# PR2017-DC_LoadMotherBoard.net
KiCad netlist of a schematic drawn in Altium Designer
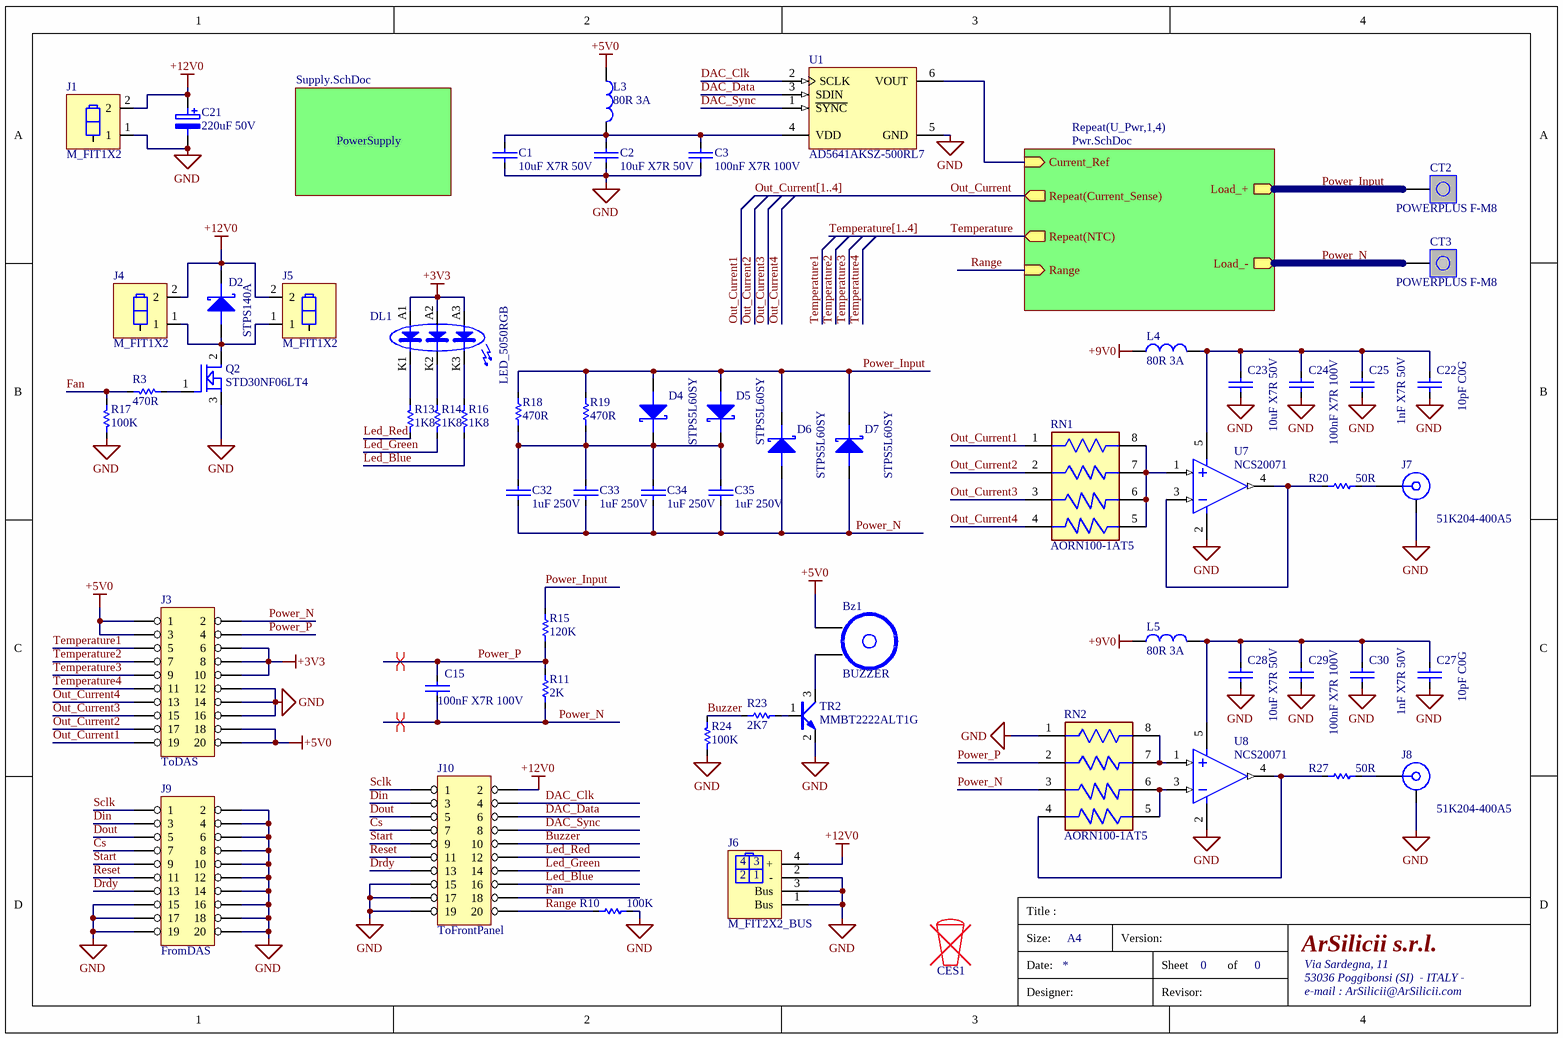
[diagram p0: PR2017-DC_LoadMotherBoard.SchDoc]

(export (version "E")
  (design (tool "Eeschema 10.0.6"))
  (components
    (comp (ref "Bz1")
      (value "BUZZER")
      (footprint "CB13PA")
      (description "Buzzer")
      (libsource (lib "Library_20-02-20") (part "BUZZER"))
    )
    (comp (ref "C1")
      (value "10uF X7R 50V")
      (footprint "1206")
      (description "Capacità")
      (fields
        (field (name "1 SUPPLIER PART NUMBER") "CL31B106KBHNNNE")
        (field (name "ARSILICII PART NUMBER") "CPC0232011")
      )
      (libsource (lib "Library_20-02-20") (part "CAP_10uF X7R 50V_1206"))
    )
    (comp (ref "C2")
      (value "10uF X7R 50V")
      (footprint "1206")
      (description "Capacità")
      (fields
        (field (name "1 SUPPLIER PART NUMBER") "CL31B106KBHNNNE")
        (field (name "ARSILICII PART NUMBER") "CPC0232011")
      )
      (libsource (lib "Library_20-02-20") (part "CAP_10uF X7R 50V_1206"))
    )
    (comp (ref "C3")
      (value "100nF X7R 100V")
      (footprint "0805")
      (description "Capacità")
      (fields
        (field (name "1 SUPPLIER PART NUMBER") "CL21B104KCFSFNG")
        (field (name "2 SUPPLIER PART NUMBER") "1907331")
      )
      (libsource (lib "Library_20-02-20") (part "CAP_100nF X7R 100V_0805"))
    )
    (comp (ref "C15")
      (value "100nF X7R 100V")
      (footprint "0805")
      (description "Capacità")
      (fields
        (field (name "1 SUPPLIER PART NUMBER") "CL21B104KCFSFNG")
        (field (name "2 SUPPLIER PART NUMBER") "1907331")
      )
      (libsource (lib "Library_20-02-20") (part "CAP_100nF X7R 100V_0805"))
    )
    (comp (ref "C21")
      (value "220uF 50V")
      (footprint "C_G55")
      (description "Capacità polarizzata")
      (fields
        (field (name "2 SUPPLIER PART NUMBER") "5194346")
        (field (name "ARSILICII PART NUMBER") "CPC0402221")
      )
      (libsource (lib "Library_20-02-20") (part "CAP_EL_220uF 50V"))
    )
    (comp (ref "C22")
      (value "10pF C0G")
      (footprint "0805")
      (description "Capacità")
      (fields (field (name "ARSILICII PART NUMBER") "CPC0614010"))
      (libsource (lib "Library_20-02-20") (part "CAP_10pF C0G_0805"))
    )
    (comp (ref "C23")
      (value "10uF X7R 50V")
      (footprint "1206")
      (description "Capacità")
      (fields
        (field (name "1 SUPPLIER PART NUMBER") "CL31B106KBHNNNE")
        (field (name "ARSILICII PART NUMBER") "CPC0232011")
      )
      (libsource (lib "Library_20-02-20") (part "CAP_10uF X7R 50V_1206"))
    )
    (comp (ref "C24")
      (value "100nF X7R 100V")
      (footprint "0805")
      (description "Capacità")
      (fields
        (field (name "1 SUPPLIER PART NUMBER") "CL21B104KCFSFNG")
        (field (name "2 SUPPLIER PART NUMBER") "1907331")
      )
      (libsource (lib "Library_20-02-20") (part "CAP_100nF X7R 100V_0805"))
    )
    (comp (ref "C25")
      (value "1nF X7R 50V")
      (footprint "0603")
      (description "Capacità")
      (fields
        (field (name "1 SUPPLIER PART NUMBER") "CC0603JRX7R9BB102")
        (field (name "ARSILICII PART NUMBER") "CPC0263001")
      )
      (libsource (lib "Library_20-02-20") (part "CAP_1nF X7R 50V_0603"))
    )
    (comp (ref "C27")
      (value "10pF C0G")
      (footprint "0805")
      (description "Capacità")
      (fields (field (name "ARSILICII PART NUMBER") "CPC0614010"))
      (libsource (lib "Library_20-02-20") (part "CAP_10pF C0G_0805"))
    )
    (comp (ref "C28")
      (value "10uF X7R 50V")
      (footprint "1206")
      (description "Capacità")
      (fields
        (field (name "1 SUPPLIER PART NUMBER") "CL31B106KBHNNNE")
        (field (name "ARSILICII PART NUMBER") "CPC0232011")
      )
      (libsource (lib "Library_20-02-20") (part "CAP_10uF X7R 50V_1206"))
    )
    (comp (ref "C29")
      (value "100nF X7R 100V")
      (footprint "0805")
      (description "Capacità")
      (fields
        (field (name "1 SUPPLIER PART NUMBER") "CL21B104KCFSFNG")
        (field (name "2 SUPPLIER PART NUMBER") "1907331")
      )
      (libsource (lib "Library_20-02-20") (part "CAP_100nF X7R 100V_0805"))
    )
    (comp (ref "C30")
      (value "1nF X7R 50V")
      (footprint "0603")
      (description "Capacità")
      (fields
        (field (name "1 SUPPLIER PART NUMBER") "CC0603JRX7R9BB102")
        (field (name "ARSILICII PART NUMBER") "CPC0263001")
      )
      (libsource (lib "Library_20-02-20") (part "CAP_1nF X7R 50V_0603"))
    )
    (comp (ref "C32")
      (value "1uF 250V")
      (footprint "POL-P15")
      (description "Capacità poliestere")
      (fields
        (field (name "ARSILICII PART NUMBER") "CPC0502002")
        (field (name "MANUFACTURER PART NUMBER") "MKTR60II4100ZB30K")
      )
      (libsource (lib "Library_20-02-20") (part "CAP_POL_1uF 250V P.15"))
    )
    (comp (ref "C33")
      (value "1uF 250V")
      (footprint "POL-P15")
      (description "Capacità poliestere")
      (fields
        (field (name "ARSILICII PART NUMBER") "CPC0502002")
        (field (name "MANUFACTURER PART NUMBER") "MKTR60II4100ZB30K")
      )
      (libsource (lib "Library_20-02-20") (part "CAP_POL_1uF 250V P.15"))
    )
    (comp (ref "C34")
      (value "1uF 250V")
      (footprint "POL-P15")
      (description "Capacità poliestere")
      (fields
        (field (name "ARSILICII PART NUMBER") "CPC0502002")
        (field (name "MANUFACTURER PART NUMBER") "MKTR60II4100ZB30K")
      )
      (libsource (lib "Library_20-02-20") (part "CAP_POL_1uF 250V P.15"))
    )
    (comp (ref "C35")
      (value "1uF 250V")
      (footprint "POL-P15")
      (description "Capacità poliestere")
      (fields
        (field (name "ARSILICII PART NUMBER") "CPC0502002")
        (field (name "MANUFACTURER PART NUMBER") "MKTR60II4100ZB30K")
      )
      (libsource (lib "Library_20-02-20") (part "CAP_POL_1uF 250V P.15"))
    )
    (comp (ref "CES1")
      (value "CESTINO")
      (footprint "Cestino1")
      (libsource (lib "Library_20-02-20") (part "CESTINO"))
    )
    (comp (ref "CT2")
      (value "POWERPLUS F-M8")
      (footprint "PowerPlus M8")
      (description "Singolo contatto")
      (fields
        (field (name "1 SUPPLIER PART NUMBER") "S98978")
        (field (name "ARSILICII PART NUMBER") "QC04000180")
      )
      (libsource (lib "Library_20-02-20") (part "PAD_POWERPLUS F-M8"))
    )
    (comp (ref "CT3")
      (value "POWERPLUS F-M8")
      (footprint "PowerPlus M8")
      (description "Singolo contatto")
      (fields
        (field (name "1 SUPPLIER PART NUMBER") "S98978")
        (field (name "ARSILICII PART NUMBER") "QC04000180")
      )
      (libsource (lib "Library_20-02-20") (part "PAD_POWERPLUS F-M8"))
    )
    (comp (ref "D2")
      (value "STPS140A")
      (footprint "SMA")
      (description "Diodo Schottky")
      (fields
        (field (name "MANUFACTURER") "STMicroelectronics")
        (field (name "1 SUPPLIER PART NUMBER") "STMSTPS140A")
      )
      (libsource (lib "Library_20-02-20") (part "DIODE SCHOTTKY_STPS140A"))
    )
    (comp (ref "D4")
      (value "STPS5L60SY")
      (footprint "SMC")
      (description "Automotive power Schottky rectifier")
      (fields (field (name "MANUFACTURER") "STM") (field (name "1 SUPPLIER PART NUMBER") "511-STPS5L60SY"))
      (libsource (lib "Library_20-02-20") (part "DIODE SCHOTTKY_STPS5L60SY"))
    )
    (comp (ref "D5")
      (value "STPS5L60SY")
      (footprint "SMC")
      (description "Automotive power Schottky rectifier")
      (fields (field (name "MANUFACTURER") "STM") (field (name "1 SUPPLIER PART NUMBER") "511-STPS5L60SY"))
      (libsource (lib "Library_20-02-20") (part "DIODE SCHOTTKY_STPS5L60SY"))
    )
    (comp (ref "D6")
      (value "STPS5L60SY")
      (footprint "SMC")
      (description "Automotive power Schottky rectifier")
      (fields (field (name "MANUFACTURER") "STM") (field (name "1 SUPPLIER PART NUMBER") "511-STPS5L60SY"))
      (libsource (lib "Library_20-02-20") (part "DIODE SCHOTTKY_STPS5L60SY"))
    )
    (comp (ref "D7")
      (value "STPS5L60SY")
      (footprint "SMC")
      (description "Automotive power Schottky rectifier")
      (fields (field (name "MANUFACTURER") "STM") (field (name "1 SUPPLIER PART NUMBER") "511-STPS5L60SY"))
      (libsource (lib "Library_20-02-20") (part "DIODE SCHOTTKY_STPS5L60SY"))
    )
    (comp (ref "DL1")
      (value "LED_5050RGB")
      (footprint "LED_5050RGB")
      (description "LED RGB")
      (libsource (lib "Library_20-02-20") (part "LED_5050RGB"))
    )
    (comp (ref "J1")
      (value "M_FIT1X2")
      (footprint "M_FIT_JR1X2V")
      (description "Mini Fit Junior 2 poli")
      (fields (field (name "ARSILICII PART NUMBER") "QA02006000") (field (name "MANUFACTURER") "Molex"))
      (libsource (lib "") (part "M_FIT1X2_1"))
    )
    (comp (ref "J3")
      (value "ToDAS")
      (footprint "IDC-20")
      (libsource (lib "Library_20-02-20") (part "HEADER 10X2"))
    )
    (comp (ref "J4")
      (value "M_FIT1X2")
      (footprint "M_FIT_JR1X2V")
      (description "Mini Fit Junior 2 poli")
      (fields (field (name "ARSILICII PART NUMBER") "QA02006000") (field (name "MANUFACTURER") "Molex"))
      (libsource (lib "") (part "M_FIT1X2_1"))
    )
    (comp (ref "J5")
      (value "M_FIT1X2")
      (footprint "M_FIT_JR1X2V")
      (description "Mini Fit Junior 2 poli")
      (fields (field (name "ARSILICII PART NUMBER") "QA02006000") (field (name "MANUFACTURER") "Molex"))
      (libsource (lib "Library_20-02-20") (part "M_FIT1X2"))
    )
    (comp (ref "J6")
      (value "M_FIT2X2_BUS")
      (footprint "M_FIT_JR2X2V")
      (description "Mini Fit Junior 4 poli")
      (fields
        (field (name "2 SUPPLIER PART NUMBER") "P6657I-04")
        (field (name "3 SUPPLIER PART NUMBER") "EY5900-W04ST")
      )
      (libsource (lib "Library_20-02-20") (part "M_FIT2X2_BUS"))
    )
    (comp (ref "J7")
      (value "51K204-400A5")
      (footprint "ROS-51K204-400A5_V")
      (description "BNC 50R Right Angle Jack, Panel Feedthrough, Up to 10 GHz, -55 to 155 degC")
      (fields (field (name "MANUFACTURER") "Rosenberger"))
      (libsource (lib "Altium Content Vault") (part "ROS-CN-1F-RF1"))
    )
    (comp (ref "J8")
      (value "51K204-400A5")
      (footprint "ROS-51K204-400A5_V")
      (description "BNC 50R Right Angle Jack, Panel Feedthrough, Up to 10 GHz, -55 to 155 degC")
      (fields (field (name "MANUFACTURER") "Rosenberger"))
      (libsource (lib "Altium Content Vault") (part "ROS-CN-1F-RF1"))
    )
    (comp (ref "J9")
      (value "FromDAS")
      (footprint "IDC-20")
      (libsource (lib "Library_20-02-20") (part "HEADER 10X2"))
    )
    (comp (ref "J10")
      (value "ToFrontPanel")
      (footprint "IDC-20")
      (libsource (lib "Library_20-02-20") (part "HEADER 10X2"))
    )
    (comp (ref "L3")
      (value "80R 3A")
      (footprint "1206")
      (description "Ferrite")
      (fields
        (field (name "1 SUPPLIER PART NUMBER") "3275550P")
        (field (name "ARSILICII PART NUMBER") "CPF0006000")
      )
      (libsource (lib "Library_20-02-20") (part "Ferrite 80R 3A"))
    )
    (comp (ref "L4")
      (value "80R 3A")
      (footprint "1206")
      (description "Ferrite")
      (fields
        (field (name "1 SUPPLIER PART NUMBER") "3275550P")
        (field (name "ARSILICII PART NUMBER") "CPF0006000")
      )
      (libsource (lib "Library_20-02-20") (part "Ferrite 80R 3A"))
    )
    (comp (ref "L5")
      (value "80R 3A")
      (footprint "1206")
      (description "Ferrite")
      (fields
        (field (name "1 SUPPLIER PART NUMBER") "3275550P")
        (field (name "ARSILICII PART NUMBER") "CPF0006000")
      )
      (libsource (lib "Library_20-02-20") (part "Ferrite 80R 3A"))
    )
    (comp (ref "Q2")
      (value "STD30NF06LT4")
      (footprint "DPAK")
      (description "N-CHANNEL 60V - 0.020 Ω - 28A IPAK/DPAK  STripFET™ II POWER MOSFET")
      (fields
        (field (name "1 SUPPLIER PART NUMBER") "STD30NF06LT4/STM")
        (field (name "ARSILICII PART NUMBER") "CPTP200030")
      )
      (libsource (lib "Library_20-02-20") (part "MOS-N STD30NF06"))
    )
    (comp (ref "R3")
      (value "470R")
      (footprint "0805")
      (description "Resistenza")
      (libsource (lib "Library_20-02-20") (part "RES_SMD"))
    )
    (comp (ref "R10")
      (value "100K")
      (footprint "0805")
      (description "Resistenza")
      (libsource (lib "Library_20-02-20") (part "RES_SMD"))
    )
    (comp (ref "R11")
      (value "2K")
      (footprint "2512")
      (description "Resistenza")
      (libsource (lib "Library_20-02-20") (part "RES_SMD"))
    )
    (comp (ref "R13")
      (value "1K8")
      (footprint "0805")
      (description "Resistenza")
      (libsource (lib "Library_20-02-20") (part "RES_SMD"))
    )
    (comp (ref "R14")
      (value "1K8")
      (footprint "0805")
      (description "Resistenza")
      (libsource (lib "Library_20-02-20") (part "RES_SMD"))
    )
    (comp (ref "R15")
      (value "120K")
      (footprint "2512")
      (description "Resistenza")
      (libsource (lib "Library_20-02-20") (part "RES_SMD"))
    )
    (comp (ref "R16")
      (value "1K8")
      (footprint "0805")
      (description "Resistenza")
      (libsource (lib "Library_20-02-20") (part "RES_SMD"))
    )
    (comp (ref "R17")
      (value "100K")
      (footprint "0805")
      (description "Resistenza")
      (libsource (lib "Library_20-02-20") (part "RES_SMD"))
    )
    (comp (ref "R18")
      (value "470R")
      (footprint "0805")
      (description "Resistenza")
      (libsource (lib "Library_20-02-20") (part "RES_SMD"))
    )
    (comp (ref "R19")
      (value "470R")
      (footprint "0805")
      (description "Resistenza")
      (libsource (lib "Library_20-02-20") (part "RES_SMD"))
    )
    (comp (ref "R20")
      (value "50R")
      (footprint "0805")
      (description "Resistenza")
      (libsource (lib "Library_20-02-20") (part "RES_SMD"))
    )
    (comp (ref "R23")
      (value "2K7")
      (footprint "0805")
      (description "Resistenza")
      (libsource (lib "Library_20-02-20") (part "RES_SMD"))
    )
    (comp (ref "R24")
      (value "100K")
      (footprint "0805")
      (description "Resistenza")
      (libsource (lib "Library_20-02-20") (part "RES_SMD"))
    )
    (comp (ref "R27")
      (value "50R")
      (footprint "0805")
      (description "Resistenza")
      (libsource (lib "Library_20-02-20") (part "RES_SMD"))
    )
    (comp (ref "RN1")
      (value "AORN100-1AT5")
      (footprint "FP-AORN100-1AT5-IPC_C")
      (description "RES NETWORK 4 RES MULT OHM 8SOIC")
      (fields (field (name "MANUFACTURER") "Vishay") (field (name "TOLERANCE") "0.1%"))
      (libsource (lib "Altium Content Vault") (part "8441eaa576eb2593bca60d5301712c1"))
    )
    (comp (ref "RN2")
      (value "AORN100-1AT5")
      (footprint "FP-AORN100-1AT5-IPC_C")
      (description "RES NETWORK 4 RES MULT OHM 8SOIC")
      (fields (field (name "MANUFACTURER") "Vishay") (field (name "TOLERANCE") "0.1%"))
      (libsource (lib "Altium Content Vault") (part "8441eaa576eb2593bca60d5301712c1"))
    )
    (comp (ref "TR2")
      (value "MMBT2222ALT1G")
      (footprint "SOT-23")
      (description "NPN Transistor")
      (fields
        (field (name "1 SUPPLIER PART NUMBER") "SCGMMBT2222ALT1G")
        (field (name "2 SUPPLIER PART NUMBER") "1459098")
      )
      (libsource (lib "Library_20-02-20") (part "NPN_MMBT2222ALT1G"))
    )
    (comp (ref "U1")
      (value "AD5641AKSZ-500RL7")
      (footprint "KS-6_L")
      (description "Single 14-Bit nanoDAC with SPI Interface, 5 V, <100 uA, -40 to +125 degC, KS-6, Pb-Free, Reel")
      (fields (field (name "GENERIC PART NUMBER") "AD5641") (field (name "MANUFACTURER") "Analog Devices"))
      (libsource (lib "Altium Content Vault") (part "ADI-AD5641-KS-6"))
    )
    (comp (ref "U7")
      (value "NCS20071")
      (footprint "SOT-553-5")
      (description "Rail-to-Rail Input/Output, 3 MHz Op Amps")
      (fields
        (field (name "1 SUPPLIER PART NUMBER") "MCP6021-E/SN-ND")
        (field (name "MANUFACTURER") "Microchip Technology")
      )
      (libsource (lib "Library_20-02-20") (part "NCS20071"))
    )
    (comp (ref "U8")
      (value "NCS20071")
      (footprint "SOT-553-5")
      (description "Rail-to-Rail Input/Output, 3 MHz Op Amps")
      (fields
        (field (name "1 SUPPLIER PART NUMBER") "MCP6021-E/SN-ND")
        (field (name "MANUFACTURER") "Microchip Technology")
      )
      (libsource (lib "Library_20-02-20") (part "NCS20071"))
    )
  )
  (nets
    (net (code "1") (name "+3V3") (class "Default")
      (node (ref "DL1") (pin "A1") (pinfunction "A1_A1") (pintype "passive"))
      (node (ref "DL1") (pin "A2") (pinfunction "A2_A2") (pintype "passive"))
      (node (ref "DL1") (pin "A3") (pinfunction "A3_A3") (pintype "passive"))
      (node (ref "J3") (pin "10") (pinfunction "10_10") (pintype "passive"))
      (node (ref "J3") (pin "6") (pinfunction "6_6") (pintype "passive"))
      (node (ref "J3") (pin "8") (pinfunction "8_8") (pintype "passive"))
    )
    (net (code "2") (name "+5V0") (class "Default")
      (node (ref "Bz1") (pin "1") (pinfunction "1_1") (pintype "passive"))
      (node (ref "J3") (pin "1") (pinfunction "1_1") (pintype "passive"))
      (node (ref "J3") (pin "18") (pinfunction "18_18") (pintype "passive"))
      (node (ref "J3") (pin "20") (pinfunction "20_20") (pintype "passive"))
      (node (ref "J3") (pin "3") (pinfunction "3_3") (pintype "passive"))
      (node (ref "L3") (pin "1") (pinfunction "1_1") (pintype "passive"))
    )
    (net (code "3") (name "+9V0") (class "Default")
      (node (ref "L4") (pin "1") (pinfunction "1_1") (pintype "passive"))
      (node (ref "L5") (pin "1") (pinfunction "1_1") (pintype "passive"))
    )
    (net (code "4") (name "+12V0") (class "Default")
      (node (ref "C21") (pin "1") (pintype "passive"))
      (node (ref "D2") (pin "K") (pinfunction "K_K") (pintype "passive"))
      (node (ref "J1") (pin "2") (pinfunction "2_2") (pintype "passive"))
      (node (ref "J10") (pin "2") (pinfunction "2_2") (pintype "passive"))
      (node (ref "J4") (pin "2") (pinfunction "2_2") (pintype "passive"))
      (node (ref "J5") (pin "2") (pinfunction "2_2") (pintype "passive"))
      (node (ref "J6") (pin "4") (pinfunction "+_4") (pintype "passive"))
    )
    (net (code "5") (name "/Buzzer") (class "Default")
      (node (ref "J10") (pin "10") (pinfunction "10_10") (pintype "passive"))
      (node (ref "R23") (pin "2") (pinfunction "2_2") (pintype "passive"))
      (node (ref "R24") (pin "2") (pinfunction "2_2") (pintype "passive"))
    )
    (net (code "6") (name "/Cs") (class "Default")
      (node (ref "J10") (pin "7") (pinfunction "7_7") (pintype "passive"))
      (node (ref "J9") (pin "7") (pinfunction "7_7") (pintype "passive"))
    )
    (net (code "7") (name "/Current_Ref") (class "Default")
      (node (ref "U1") (pin "6") (pinfunction "VOUT_6") (pintype "tri_state"))
    )
    (net (code "8") (name "/DAC_Clk") (class "Default")
      (node (ref "J10") (pin "4") (pinfunction "4_4") (pintype "passive"))
      (node (ref "U1") (pin "2") (pinfunction "SCLK_2") (pintype "input"))
    )
    (net (code "9") (name "/DAC_Data") (class "Default")
      (node (ref "J10") (pin "6") (pinfunction "6_6") (pintype "passive"))
      (node (ref "U1") (pin "3") (pinfunction "SDIN_3") (pintype "input"))
    )
    (net (code "10") (name "/DAC_Sync") (class "Default")
      (node (ref "J10") (pin "8") (pinfunction "8_8") (pintype "passive"))
      (node (ref "U1") (pin "1") (pinfunction "~{SYNC}_1") (pintype "input"))
    )
    (net (code "11") (name "/Din") (class "Default")
      (node (ref "J10") (pin "3") (pinfunction "3_3") (pintype "passive"))
      (node (ref "J9") (pin "3") (pinfunction "3_3") (pintype "passive"))
    )
    (net (code "12") (name "/Dout") (class "Default")
      (node (ref "J10") (pin "5") (pinfunction "5_5") (pintype "passive"))
      (node (ref "J9") (pin "5") (pinfunction "5_5") (pintype "passive"))
    )
    (net (code "13") (name "/Drdy") (class "Default")
      (node (ref "J10") (pin "13") (pinfunction "13_13") (pintype "passive"))
      (node (ref "J9") (pin "13") (pinfunction "13_13") (pintype "passive"))
    )
    (net (code "14") (name "/Fan") (class "Default")
      (node (ref "J10") (pin "18") (pinfunction "18_18") (pintype "passive"))
      (node (ref "R17") (pin "2") (pinfunction "2_2") (pintype "passive"))
      (node (ref "R3") (pin "2") (pinfunction "2_2") (pintype "passive"))
    )
    (net (code "15") (name "/Led_Blue") (class "Default")
      (node (ref "J10") (pin "16") (pinfunction "16_16") (pintype "passive"))
      (node (ref "R16") (pin "1") (pinfunction "1_1") (pintype "passive"))
    )
    (net (code "16") (name "/Led_Green") (class "Default")
      (node (ref "J10") (pin "14") (pinfunction "14_14") (pintype "passive"))
      (node (ref "R14") (pin "1") (pinfunction "1_1") (pintype "passive"))
    )
    (net (code "17") (name "/Led_Red") (class "Default")
      (node (ref "J10") (pin "12") (pinfunction "12_12") (pintype "passive"))
      (node (ref "R13") (pin "1") (pinfunction "1_1") (pintype "passive"))
    )
    (net (code "19") (name "/Out_Current1") (class "Default")
      (node (ref "J3") (pin "19") (pinfunction "19_19") (pintype "passive"))
      (node (ref "RN1") (pin "1") (pinfunction "1_1") (pintype "passive"))
    )
    (net (code "20") (name "/Out_Current2") (class "Default")
      (node (ref "J3") (pin "17") (pinfunction "17_17") (pintype "passive"))
      (node (ref "RN1") (pin "2") (pinfunction "2_2") (pintype "passive"))
    )
    (net (code "21") (name "/Out_Current3") (class "Default")
      (node (ref "J3") (pin "15") (pinfunction "15_15") (pintype "passive"))
      (node (ref "RN1") (pin "3") (pinfunction "3_3") (pintype "passive"))
    )
    (net (code "22") (name "/Out_Current4") (class "Default")
      (node (ref "J3") (pin "13") (pinfunction "13_13") (pintype "passive"))
      (node (ref "RN1") (pin "4") (pinfunction "4_4") (pintype "passive"))
    )
    (net (code "24") (name "/Power_Input") (class "Default")
      (node (ref "CT2") (pin "1") (pinfunction "1_1") (pintype "passive"))
      (node (ref "D4") (pin "A") (pinfunction "A_A") (pintype "passive"))
      (node (ref "D5") (pin "A") (pinfunction "A_A") (pintype "passive"))
      (node (ref "D6") (pin "K") (pinfunction "K_K") (pintype "passive"))
      (node (ref "D7") (pin "K") (pinfunction "K_K") (pintype "passive"))
      (node (ref "R15") (pin "1") (pinfunction "1_1") (pintype "passive"))
      (node (ref "R18") (pin "1") (pinfunction "1_1") (pintype "passive"))
      (node (ref "R19") (pin "1") (pinfunction "1_1") (pintype "passive"))
    )
    (net (code "25") (name "/Power_N") (class "Default")
      (node (ref "C15") (pin "2") (pintype "passive"))
      (node (ref "C32") (pin "2") (pintype "passive"))
      (node (ref "C33") (pin "2") (pintype "passive"))
      (node (ref "C34") (pin "2") (pintype "passive"))
      (node (ref "C35") (pin "2") (pintype "passive"))
      (node (ref "CT3") (pin "1") (pinfunction "1_1") (pintype "passive"))
      (node (ref "D6") (pin "A") (pinfunction "A_A") (pintype "passive"))
      (node (ref "D7") (pin "A") (pinfunction "A_A") (pintype "passive"))
      (node (ref "J3") (pin "2") (pinfunction "2_2") (pintype "passive"))
      (node (ref "R11") (pin "2") (pinfunction "2_2") (pintype "passive"))
      (node (ref "RN2") (pin "3") (pinfunction "3_3") (pintype "passive"))
    )
    (net (code "26") (name "/Power_P") (class "Default")
      (node (ref "C15") (pin "1") (pintype "passive"))
      (node (ref "J3") (pin "4") (pinfunction "4_4") (pintype "passive"))
      (node (ref "R11") (pin "1") (pinfunction "1_1") (pintype "passive"))
      (node (ref "R15") (pin "2") (pinfunction "2_2") (pintype "passive"))
      (node (ref "RN2") (pin "2") (pinfunction "2_2") (pintype "passive"))
    )
    (net (code "27") (name "/Range") (class "Default")
      (node (ref "J10") (pin "20") (pinfunction "20_20") (pintype "passive"))
      (node (ref "R10") (pin "2") (pinfunction "2_2") (pintype "passive"))
    )
    (net (code "28") (name "/Reset") (class "Default")
      (node (ref "J10") (pin "11") (pinfunction "11_11") (pintype "passive"))
      (node (ref "J9") (pin "11") (pinfunction "11_11") (pintype "passive"))
    )
    (net (code "29") (name "/Sclk") (class "Default")
      (node (ref "J10") (pin "1") (pinfunction "1_1") (pintype "passive"))
      (node (ref "J9") (pin "1") (pinfunction "1_1") (pintype "passive"))
    )
    (net (code "30") (name "/Start") (class "Default")
      (node (ref "J10") (pin "9") (pinfunction "9_9") (pintype "passive"))
      (node (ref "J9") (pin "9") (pinfunction "9_9") (pintype "passive"))
    )
    (net (code "32") (name "/Temperature1") (class "Default")
      (node (ref "J3") (pin "5") (pinfunction "5_5") (pintype "passive"))
    )
    (net (code "33") (name "/Temperature2") (class "Default")
      (node (ref "J3") (pin "7") (pinfunction "7_7") (pintype "passive"))
    )
    (net (code "34") (name "/Temperature3") (class "Default")
      (node (ref "J3") (pin "9") (pinfunction "9_9") (pintype "passive"))
    )
    (net (code "35") (name "/Temperature4") (class "Default")
      (node (ref "J3") (pin "11") (pinfunction "11_11") (pintype "passive"))
    )
    (net (code "37") (name "GND") (class "Default")
      (node (ref "C1") (pin "2") (pintype "passive"))
      (node (ref "C2") (pin "2") (pintype "passive"))
      (node (ref "C21") (pin "2") (pintype "passive"))
      (node (ref "C22") (pin "2") (pintype "passive"))
      (node (ref "C23") (pin "2") (pintype "passive"))
      (node (ref "C24") (pin "2") (pintype "passive"))
      (node (ref "C25") (pin "2") (pintype "passive"))
      (node (ref "C27") (pin "2") (pintype "passive"))
      (node (ref "C28") (pin "2") (pintype "passive"))
      (node (ref "C29") (pin "2") (pintype "passive"))
      (node (ref "C3") (pin "2") (pintype "passive"))
      (node (ref "C30") (pin "2") (pintype "passive"))
      (node (ref "J1") (pin "1") (pinfunction "1_1") (pintype "passive"))
      (node (ref "J10") (pin "15") (pinfunction "15_15") (pintype "passive"))
      (node (ref "J10") (pin "17") (pinfunction "17_17") (pintype "passive"))
      (node (ref "J10") (pin "19") (pinfunction "19_19") (pintype "passive"))
      (node (ref "J3") (pin "12") (pinfunction "12_12") (pintype "passive"))
      (node (ref "J3") (pin "14") (pinfunction "14_14") (pintype "passive"))
      (node (ref "J3") (pin "16") (pinfunction "16_16") (pintype "passive"))
      (node (ref "J6") (pin "1") (pinfunction "Bus_1") (pintype "passive"))
      (node (ref "J6") (pin "2") (pinfunction "-_2") (pintype "passive"))
      (node (ref "J6") (pin "3") (pinfunction "Bus_3") (pintype "passive"))
      (node (ref "J7") (pin "MH") (pinfunction "MH_MH") (pintype "passive"))
      (node (ref "J8") (pin "MH") (pinfunction "MH_MH") (pintype "passive"))
      (node (ref "J9") (pin "10") (pinfunction "10_10") (pintype "passive"))
      (node (ref "J9") (pin "12") (pinfunction "12_12") (pintype "passive"))
      (node (ref "J9") (pin "14") (pinfunction "14_14") (pintype "passive"))
      (node (ref "J9") (pin "15") (pinfunction "15_15") (pintype "passive"))
      (node (ref "J9") (pin "16") (pinfunction "16_16") (pintype "passive"))
      (node (ref "J9") (pin "17") (pinfunction "17_17") (pintype "passive"))
      (node (ref "J9") (pin "18") (pinfunction "18_18") (pintype "passive"))
      (node (ref "J9") (pin "19") (pinfunction "19_19") (pintype "passive"))
      (node (ref "J9") (pin "2") (pinfunction "2_2") (pintype "passive"))
      (node (ref "J9") (pin "20") (pinfunction "20_20") (pintype "passive"))
      (node (ref "J9") (pin "4") (pinfunction "4_4") (pintype "passive"))
      (node (ref "J9") (pin "6") (pinfunction "6_6") (pintype "passive"))
      (node (ref "J9") (pin "8") (pinfunction "8_8") (pintype "passive"))
      (node (ref "Q2") (pin "3") (pinfunction "SOURCE_3") (pintype "passive"))
      (node (ref "R10") (pin "1") (pinfunction "1_1") (pintype "passive"))
      (node (ref "R17") (pin "1") (pinfunction "1_1") (pintype "passive"))
      (node (ref "R24") (pin "1") (pinfunction "1_1") (pintype "passive"))
      (node (ref "RN2") (pin "1") (pinfunction "1_1") (pintype "passive"))
      (node (ref "TR2") (pin "2") (pinfunction "E_2") (pintype "passive"))
      (node (ref "U1") (pin "5") (pinfunction "GND_5") (pintype "power_in"))
      (node (ref "U7") (pin "2") (pintype "power_in"))
      (node (ref "U8") (pin "2") (pintype "power_in"))
    )
    (net (code "38") (name "Net-(C22-Pad1)") (class "Default")
      (node (ref "C22") (pin "1") (pintype "passive"))
      (node (ref "C23") (pin "1") (pintype "passive"))
      (node (ref "C24") (pin "1") (pintype "passive"))
      (node (ref "C25") (pin "1") (pintype "passive"))
      (node (ref "L4") (pin "2") (pinfunction "2_2") (pintype "passive"))
      (node (ref "U7") (pin "5") (pintype "power_in"))
    )
    (net (code "39") (name "Net-(C27-Pad1)") (class "Default")
      (node (ref "C27") (pin "1") (pintype "passive"))
      (node (ref "C28") (pin "1") (pintype "passive"))
      (node (ref "C29") (pin "1") (pintype "passive"))
      (node (ref "C30") (pin "1") (pintype "passive"))
      (node (ref "L5") (pin "2") (pinfunction "2_2") (pintype "passive"))
      (node (ref "U8") (pin "5") (pintype "power_in"))
    )
    (net (code "40") (name "Net-(C32-Pad1)") (class "Default")
      (node (ref "C32") (pin "1") (pintype "passive"))
      (node (ref "C33") (pin "1") (pintype "passive"))
      (node (ref "C34") (pin "1") (pintype "passive"))
      (node (ref "C35") (pin "1") (pintype "passive"))
      (node (ref "D4") (pin "K") (pinfunction "K_K") (pintype "passive"))
      (node (ref "D5") (pin "K") (pinfunction "K_K") (pintype "passive"))
      (node (ref "R18") (pin "2") (pinfunction "2_2") (pintype "passive"))
      (node (ref "R19") (pin "2") (pinfunction "2_2") (pintype "passive"))
    )
    (net (code "41") (name "Net-(DL1-PadK1)") (class "Default")
      (node (ref "DL1") (pin "K1") (pinfunction "K1_K1") (pintype "passive"))
      (node (ref "R13") (pin "2") (pinfunction "2_2") (pintype "passive"))
    )
    (net (code "42") (name "Net-(DL1-PadK2)") (class "Default")
      (node (ref "DL1") (pin "K2") (pinfunction "K2_K2") (pintype "passive"))
      (node (ref "R14") (pin "2") (pinfunction "2_2") (pintype "passive"))
    )
    (net (code "43") (name "Net-(DL1-PadK3)") (class "Default")
      (node (ref "DL1") (pin "K3") (pinfunction "K3_K3") (pintype "passive"))
      (node (ref "R16") (pin "2") (pinfunction "2_2") (pintype "passive"))
    )
    (net (code "44") (name "Net-(J7-Pad1)") (class "Default")
      (node (ref "J7") (pin "1") (pinfunction "1_1") (pintype "passive"))
      (node (ref "R20") (pin "1") (pinfunction "1_1") (pintype "passive"))
    )
    (net (code "45") (name "Net-(J8-Pad1)") (class "Default")
      (node (ref "J8") (pin "1") (pinfunction "1_1") (pintype "passive"))
      (node (ref "R27") (pin "1") (pinfunction "1_1") (pintype "passive"))
    )
    (net (code "46") (name "Net-(Q2-DRAIN)") (class "Default")
      (node (ref "D2") (pin "A") (pinfunction "A_A") (pintype "passive"))
      (node (ref "J4") (pin "1") (pinfunction "1_1") (pintype "passive"))
      (node (ref "J5") (pin "1") (pinfunction "1_1") (pintype "passive"))
      (node (ref "Q2") (pin "2") (pinfunction "DRAIN_2") (pintype "passive"))
    )
    (net (code "47") (name "Net-(Q2-GATE)") (class "Default")
      (node (ref "Q2") (pin "1") (pinfunction "GATE_1") (pintype "passive"))
      (node (ref "R3") (pin "1") (pinfunction "1_1") (pintype "passive"))
    )
    (net (code "48") (name "Net-(R20-Pad2)") (class "Default")
      (node (ref "R20") (pin "2") (pinfunction "2_2") (pintype "passive"))
      (node (ref "U7") (pin "3") (pintype "input"))
      (node (ref "U7") (pin "4") (pintype "output"))
    )
    (net (code "49") (name "Net-(R27-Pad2)") (class "Default")
      (node (ref "R27") (pin "2") (pinfunction "2_2") (pintype "passive"))
      (node (ref "RN2") (pin "4") (pinfunction "4_4") (pintype "passive"))
      (node (ref "U8") (pin "4") (pintype "output"))
    )
    (net (code "50") (name "Net-(RN1-Pad5)") (class "Default")
      (node (ref "RN1") (pin "5") (pinfunction "5_5") (pintype "passive"))
      (node (ref "RN1") (pin "6") (pinfunction "6_6") (pintype "passive"))
      (node (ref "RN1") (pin "7") (pinfunction "7_7") (pintype "passive"))
      (node (ref "RN1") (pin "8") (pinfunction "8_8") (pintype "passive"))
      (node (ref "U7") (pin "1") (pintype "input"))
    )
    (net (code "51") (name "Net-(RN2-Pad5)") (class "Default")
      (node (ref "RN2") (pin "5") (pinfunction "5_5") (pintype "passive"))
      (node (ref "RN2") (pin "6") (pinfunction "6_6") (pintype "passive"))
      (node (ref "U8") (pin "3") (pintype "input"))
    )
    (net (code "52") (name "Net-(RN2-Pad7)") (class "Default")
      (node (ref "RN2") (pin "7") (pinfunction "7_7") (pintype "passive"))
      (node (ref "RN2") (pin "8") (pinfunction "8_8") (pintype "passive"))
      (node (ref "U8") (pin "1") (pintype "input"))
    )
    (net (code "53") (name "Net-(TR2-B)") (class "Default")
      (node (ref "R23") (pin "1") (pinfunction "1_1") (pintype "passive"))
      (node (ref "TR2") (pin "1") (pinfunction "B_1") (pintype "passive"))
    )
    (net (code "54") (name "Net-(TR2-C)") (class "Default")
      (node (ref "Bz1") (pin "2") (pinfunction "2_2") (pintype "passive"))
      (node (ref "TR2") (pin "3") (pinfunction "C_3") (pintype "passive"))
    )
    (net (code "55") (name "Net-(U1-VDD)") (class "Default")
      (node (ref "C1") (pin "1") (pintype "passive"))
      (node (ref "C2") (pin "1") (pintype "passive"))
      (node (ref "C3") (pin "1") (pintype "passive"))
      (node (ref "L3") (pin "2") (pinfunction "2_2") (pintype "passive"))
      (node (ref "U1") (pin "4") (pinfunction "VDD_4") (pintype "power_in"))
    )
  )
)
